# esquema.net
KiCad netlist of a schematic drawn in EAGLE
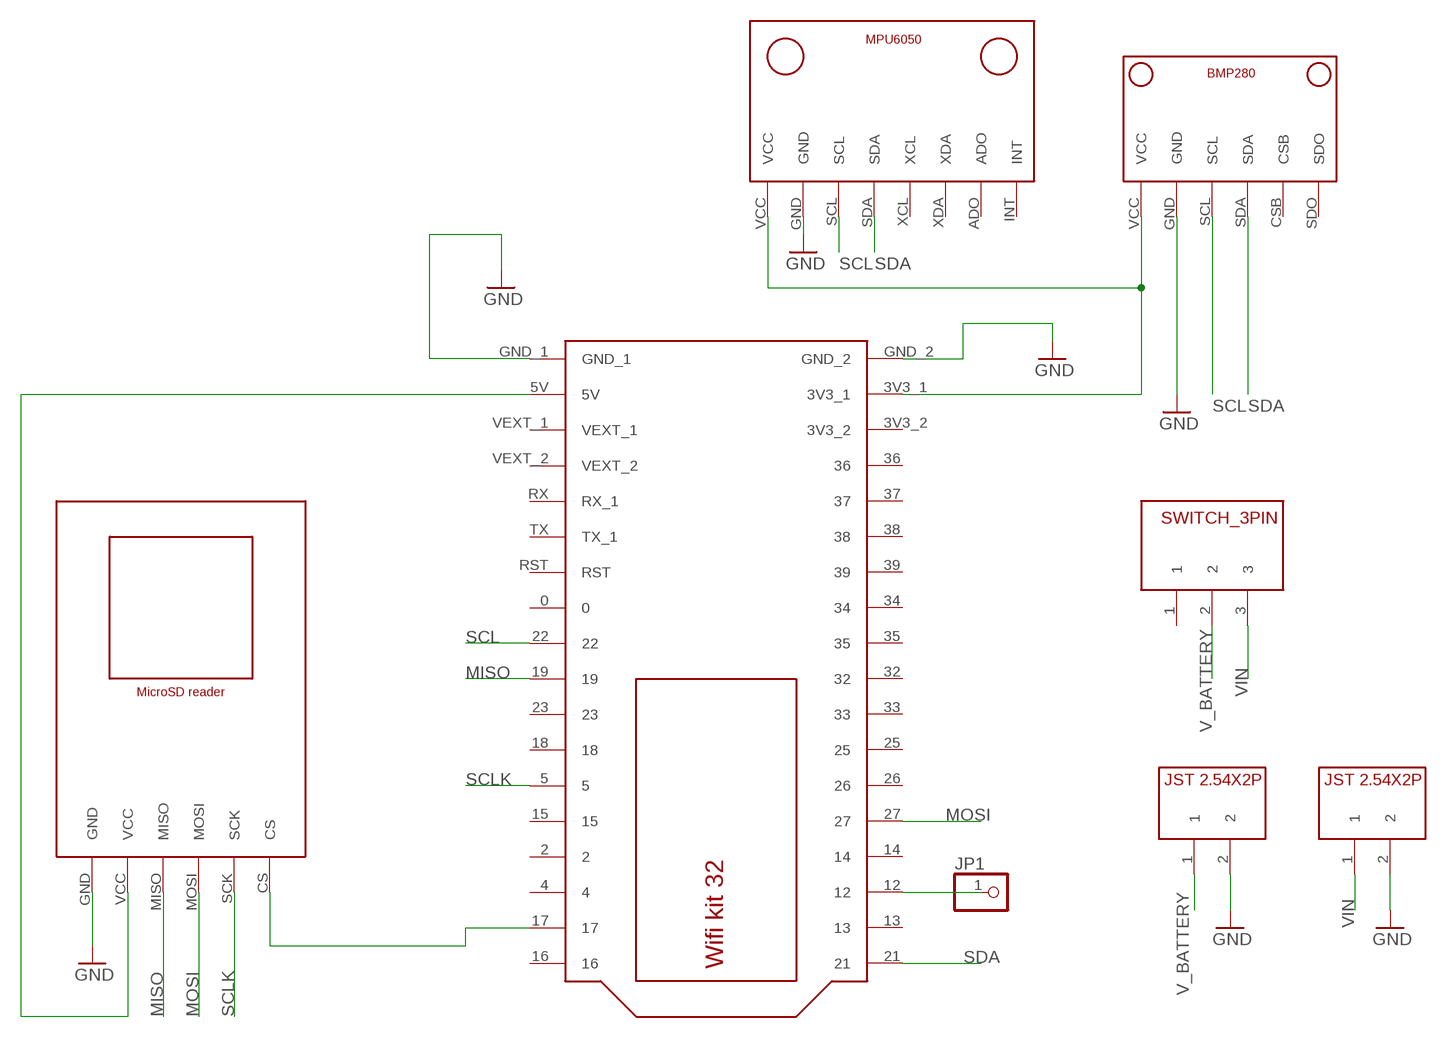
[diagram p0: schematic, sheet 1]

(export (version "E")
  (design (tool "Eeschema 10.0.6"))
  (components
    (comp (ref "JP1")
      (value "PINHD-1X1")
      (footprint "eagle-import:1X01")
      (libsource (lib "eagle-import") (part "PINHD-1X1"))
    )
    (comp (ref "U$1")
      (value "BMP280V1")
      (footprint "eagle-import:BMP280_FOOTPRINT")
      (libsource (lib "eagle-import") (part "BMP280V1"))
    )
    (comp (ref "U$2")
      (value "MICROSD_READER")
      (footprint "eagle-import:MICROSD_READER_FOOTPRINT")
      (libsource (lib "eagle-import") (part "MICROSD_READER"))
    )
    (comp (ref "U$3")
      (value "MPU6050V1")
      (footprint "eagle-import:MPU6050_FOOTPRINT")
      (libsource (lib "eagle-import") (part "MPU6050V1"))
    )
    (comp (ref "U$4")
      (value "WIFI_KIT32")
      (footprint "eagle-import:WIFI_KIT32")
      (libsource (lib "eagle-import") (part "WIFI_KIT32"))
    )
    (comp (ref "U$5")
      (value "JST2.54X2P")
      (footprint "eagle-import:JST2.54X2P_FOOTPRINT")
      (libsource (lib "eagle-import") (part "JST2.54X2P"))
    )
    (comp (ref "U$6")
      (value "SWITCH_3PIN")
      (footprint "eagle-import:SWITCH_3PIN")
      (libsource (lib "eagle-import") (part "SWITCH_3PIN"))
    )
    (comp (ref "U$7")
      (value "JST2.54X2P")
      (footprint "eagle-import:JST2.54X2P_FOOTPRINT")
      (libsource (lib "eagle-import") (part "JST2.54X2P"))
    )
  )
  (nets
    (net (code "1") (name "/MISO") (class "Default")
      (node (ref "U$2") (pin "MISO") (pinfunction "MISO_MISO") (pintype "bidirectional"))
      (node (ref "U$4") (pin "19") (pinfunction "19_19") (pintype "bidirectional"))
    )
    (net (code "2") (name "/MOSI") (class "Default")
      (node (ref "U$2") (pin "MOSI") (pinfunction "MOSI_MOSI") (pintype "bidirectional"))
      (node (ref "U$4") (pin "27") (pinfunction "27_27") (pintype "bidirectional"))
    )
    (net (code "3") (name "/SCL") (class "Default")
      (node (ref "U$1") (pin "SCL") (pinfunction "SCL_SCL") (pintype "bidirectional"))
      (node (ref "U$3") (pin "SCL") (pinfunction "SCL_SCL") (pintype "bidirectional"))
      (node (ref "U$4") (pin "22") (pinfunction "22_22") (pintype "bidirectional"))
    )
    (net (code "4") (name "/SCLK") (class "Default")
      (node (ref "U$2") (pin "SCK") (pinfunction "SCK_SCK") (pintype "bidirectional"))
      (node (ref "U$4") (pin "5") (pinfunction "5_5") (pintype "bidirectional"))
    )
    (net (code "5") (name "/SDA") (class "Default")
      (node (ref "U$1") (pin "SDA") (pinfunction "SDA_SDA") (pintype "bidirectional"))
      (node (ref "U$3") (pin "SDA") (pinfunction "SDA_SDA") (pintype "bidirectional"))
      (node (ref "U$4") (pin "21") (pinfunction "21_21") (pintype "bidirectional"))
    )
    (net (code "6") (name "/VIN") (class "Default")
      (node (ref "U$6") (pin "3") (pinfunction "3_3") (pintype "bidirectional"))
      (node (ref "U$7") (pin "1") (pinfunction "1_1") (pintype "bidirectional"))
    )
    (net (code "7") (name "/V_BATTERY") (class "Default")
      (node (ref "U$5") (pin "1") (pinfunction "1_1") (pintype "bidirectional"))
      (node (ref "U$6") (pin "2") (pinfunction "2_2") (pintype "bidirectional"))
    )
    (net (code "8") (name "GND") (class "Default")
      (node (ref "U$1") (pin "GND") (pinfunction "GND_GND") (pintype "bidirectional"))
      (node (ref "U$2") (pin "GND") (pinfunction "GND_GND") (pintype "bidirectional"))
      (node (ref "U$3") (pin "GND") (pinfunction "GND_GND") (pintype "bidirectional"))
      (node (ref "U$4") (pin "GND_1") (pinfunction "GND_1_GND_1") (pintype "bidirectional"))
      (node (ref "U$4") (pin "GND_2") (pinfunction "GND_2_GND_2") (pintype "bidirectional"))
      (node (ref "U$5") (pin "2") (pinfunction "2_2") (pintype "bidirectional"))
      (node (ref "U$7") (pin "2") (pinfunction "2_2") (pintype "bidirectional"))
    )
    (net (code "9") (name "Net-(JP1-Pad1)") (class "Default")
      (node (ref "JP1") (pin "1") (pinfunction "1_1") (pintype "passive"))
      (node (ref "U$4") (pin "12") (pinfunction "12_12") (pintype "bidirectional"))
    )
    (net (code "10") (name "Net-(U$1-PadVCC)") (class "Default")
      (node (ref "U$1") (pin "VCC") (pinfunction "VCC_VCC") (pintype "bidirectional"))
      (node (ref "U$3") (pin "VCC") (pinfunction "VCC_VCC") (pintype "bidirectional"))
      (node (ref "U$4") (pin "3V3_1") (pinfunction "3V3_1_3V3_1") (pintype "bidirectional"))
    )
    (net (code "11") (name "Net-(U$2-PadCS)") (class "Default")
      (node (ref "U$2") (pin "CS") (pinfunction "CS_CS") (pintype "bidirectional"))
      (node (ref "U$4") (pin "17") (pinfunction "17_17") (pintype "bidirectional"))
    )
    (net (code "12") (name "Net-(U$2-PadVCC)") (class "Default")
      (node (ref "U$2") (pin "VCC") (pinfunction "VCC_VCC") (pintype "bidirectional"))
      (node (ref "U$4") (pin "5V") (pinfunction "5V_5V") (pintype "bidirectional"))
    )
    (net (code "13") (name "unconnected-(U$1-PadCSB)") (class "Default")
      (node (ref "U$1") (pin "CSB") (pinfunction "CSB_CSB") (pintype "bidirectional"))
    )
    (net (code "14") (name "unconnected-(U$1-PadSDO)") (class "Default")
      (node (ref "U$1") (pin "SDO") (pinfunction "SDO_SDO") (pintype "bidirectional"))
    )
    (net (code "15") (name "unconnected-(U$3-PadADO)") (class "Default")
      (node (ref "U$3") (pin "ADO") (pinfunction "ADO_ADO") (pintype "bidirectional"))
    )
    (net (code "16") (name "unconnected-(U$3-PadINT)") (class "Default")
      (node (ref "U$3") (pin "INT") (pinfunction "INT_INT") (pintype "bidirectional"))
    )
    (net (code "17") (name "unconnected-(U$3-PadXCL)") (class "Default")
      (node (ref "U$3") (pin "XCL") (pinfunction "XCL_XCL") (pintype "bidirectional"))
    )
    (net (code "18") (name "unconnected-(U$3-PadXDA)") (class "Default")
      (node (ref "U$3") (pin "XDA") (pinfunction "XDA_XDA") (pintype "bidirectional"))
    )
    (net (code "19") (name "unconnected-(U$4-Pad0)") (class "Default")
      (node (ref "U$4") (pin "0") (pinfunction "0_0") (pintype "bidirectional"))
    )
    (net (code "20") (name "unconnected-(U$4-Pad2)") (class "Default")
      (node (ref "U$4") (pin "2") (pinfunction "2_2") (pintype "bidirectional"))
    )
    (net (code "21") (name "unconnected-(U$4-Pad3V3_2)") (class "Default")
      (node (ref "U$4") (pin "3V3_2") (pinfunction "3V3_2_3V3_2") (pintype "bidirectional"))
    )
    (net (code "22") (name "unconnected-(U$4-Pad4)") (class "Default")
      (node (ref "U$4") (pin "4") (pinfunction "4_4") (pintype "bidirectional"))
    )
    (net (code "23") (name "unconnected-(U$4-Pad13)") (class "Default")
      (node (ref "U$4") (pin "13") (pinfunction "13_13") (pintype "bidirectional"))
    )
    (net (code "24") (name "unconnected-(U$4-Pad14)") (class "Default")
      (node (ref "U$4") (pin "14") (pinfunction "14_14") (pintype "bidirectional"))
    )
    (net (code "25") (name "unconnected-(U$4-Pad15)") (class "Default")
      (node (ref "U$4") (pin "15") (pinfunction "15_15") (pintype "bidirectional"))
    )
    (net (code "26") (name "unconnected-(U$4-Pad16)") (class "Default")
      (node (ref "U$4") (pin "16") (pinfunction "16_16") (pintype "bidirectional"))
    )
    (net (code "27") (name "unconnected-(U$4-Pad18)") (class "Default")
      (node (ref "U$4") (pin "18") (pinfunction "18_18") (pintype "bidirectional"))
    )
    (net (code "28") (name "unconnected-(U$4-Pad23)") (class "Default")
      (node (ref "U$4") (pin "23") (pinfunction "23_23") (pintype "bidirectional"))
    )
    (net (code "29") (name "unconnected-(U$4-Pad25)") (class "Default")
      (node (ref "U$4") (pin "25") (pinfunction "25_25") (pintype "bidirectional"))
    )
    (net (code "30") (name "unconnected-(U$4-Pad26)") (class "Default")
      (node (ref "U$4") (pin "26") (pinfunction "26_26") (pintype "bidirectional"))
    )
    (net (code "31") (name "unconnected-(U$4-Pad32)") (class "Default")
      (node (ref "U$4") (pin "32") (pinfunction "32_32") (pintype "bidirectional"))
    )
    (net (code "32") (name "unconnected-(U$4-Pad33)") (class "Default")
      (node (ref "U$4") (pin "33") (pinfunction "33_33") (pintype "bidirectional"))
    )
    (net (code "33") (name "unconnected-(U$4-Pad34)") (class "Default")
      (node (ref "U$4") (pin "34") (pinfunction "34_34") (pintype "bidirectional"))
    )
    (net (code "34") (name "unconnected-(U$4-Pad35)") (class "Default")
      (node (ref "U$4") (pin "35") (pinfunction "35_35") (pintype "bidirectional"))
    )
    (net (code "35") (name "unconnected-(U$4-Pad36)") (class "Default")
      (node (ref "U$4") (pin "36") (pinfunction "36_36") (pintype "bidirectional"))
    )
    (net (code "36") (name "unconnected-(U$4-Pad37)") (class "Default")
      (node (ref "U$4") (pin "37") (pinfunction "37_37") (pintype "bidirectional"))
    )
    (net (code "37") (name "unconnected-(U$4-Pad38)") (class "Default")
      (node (ref "U$4") (pin "38") (pinfunction "38_38") (pintype "bidirectional"))
    )
    (net (code "38") (name "unconnected-(U$4-Pad39)") (class "Default")
      (node (ref "U$4") (pin "39") (pinfunction "39_39") (pintype "bidirectional"))
    )
    (net (code "39") (name "unconnected-(U$4-PadRST)") (class "Default")
      (node (ref "U$4") (pin "RST") (pinfunction "RST_RST") (pintype "bidirectional"))
    )
    (net (code "40") (name "unconnected-(U$4-PadVEXT_1)") (class "Default")
      (node (ref "U$4") (pin "VEXT_1") (pinfunction "VEXT_1_VEXT_1") (pintype "bidirectional"))
    )
    (net (code "41") (name "unconnected-(U$4-PadVEXT_2)") (class "Default")
      (node (ref "U$4") (pin "VEXT_2") (pinfunction "VEXT_2_VEXT_2") (pintype "bidirectional"))
    )
    (net (code "42") (name "unconnected-(U$4-RX_1-PadRX)") (class "Default")
      (node (ref "U$4") (pin "RX") (pinfunction "RX_1_RX") (pintype "bidirectional"))
    )
    (net (code "43") (name "unconnected-(U$4-TX_1-PadTX)") (class "Default")
      (node (ref "U$4") (pin "TX") (pinfunction "TX_1_TX") (pintype "bidirectional"))
    )
    (net (code "44") (name "unconnected-(U$6-Pad1)") (class "Default")
      (node (ref "U$6") (pin "1") (pinfunction "1_1") (pintype "bidirectional"))
    )
  )
)
